# STM32_MCU.net
KiCad netlist of a schematic drawn in Altium Designer
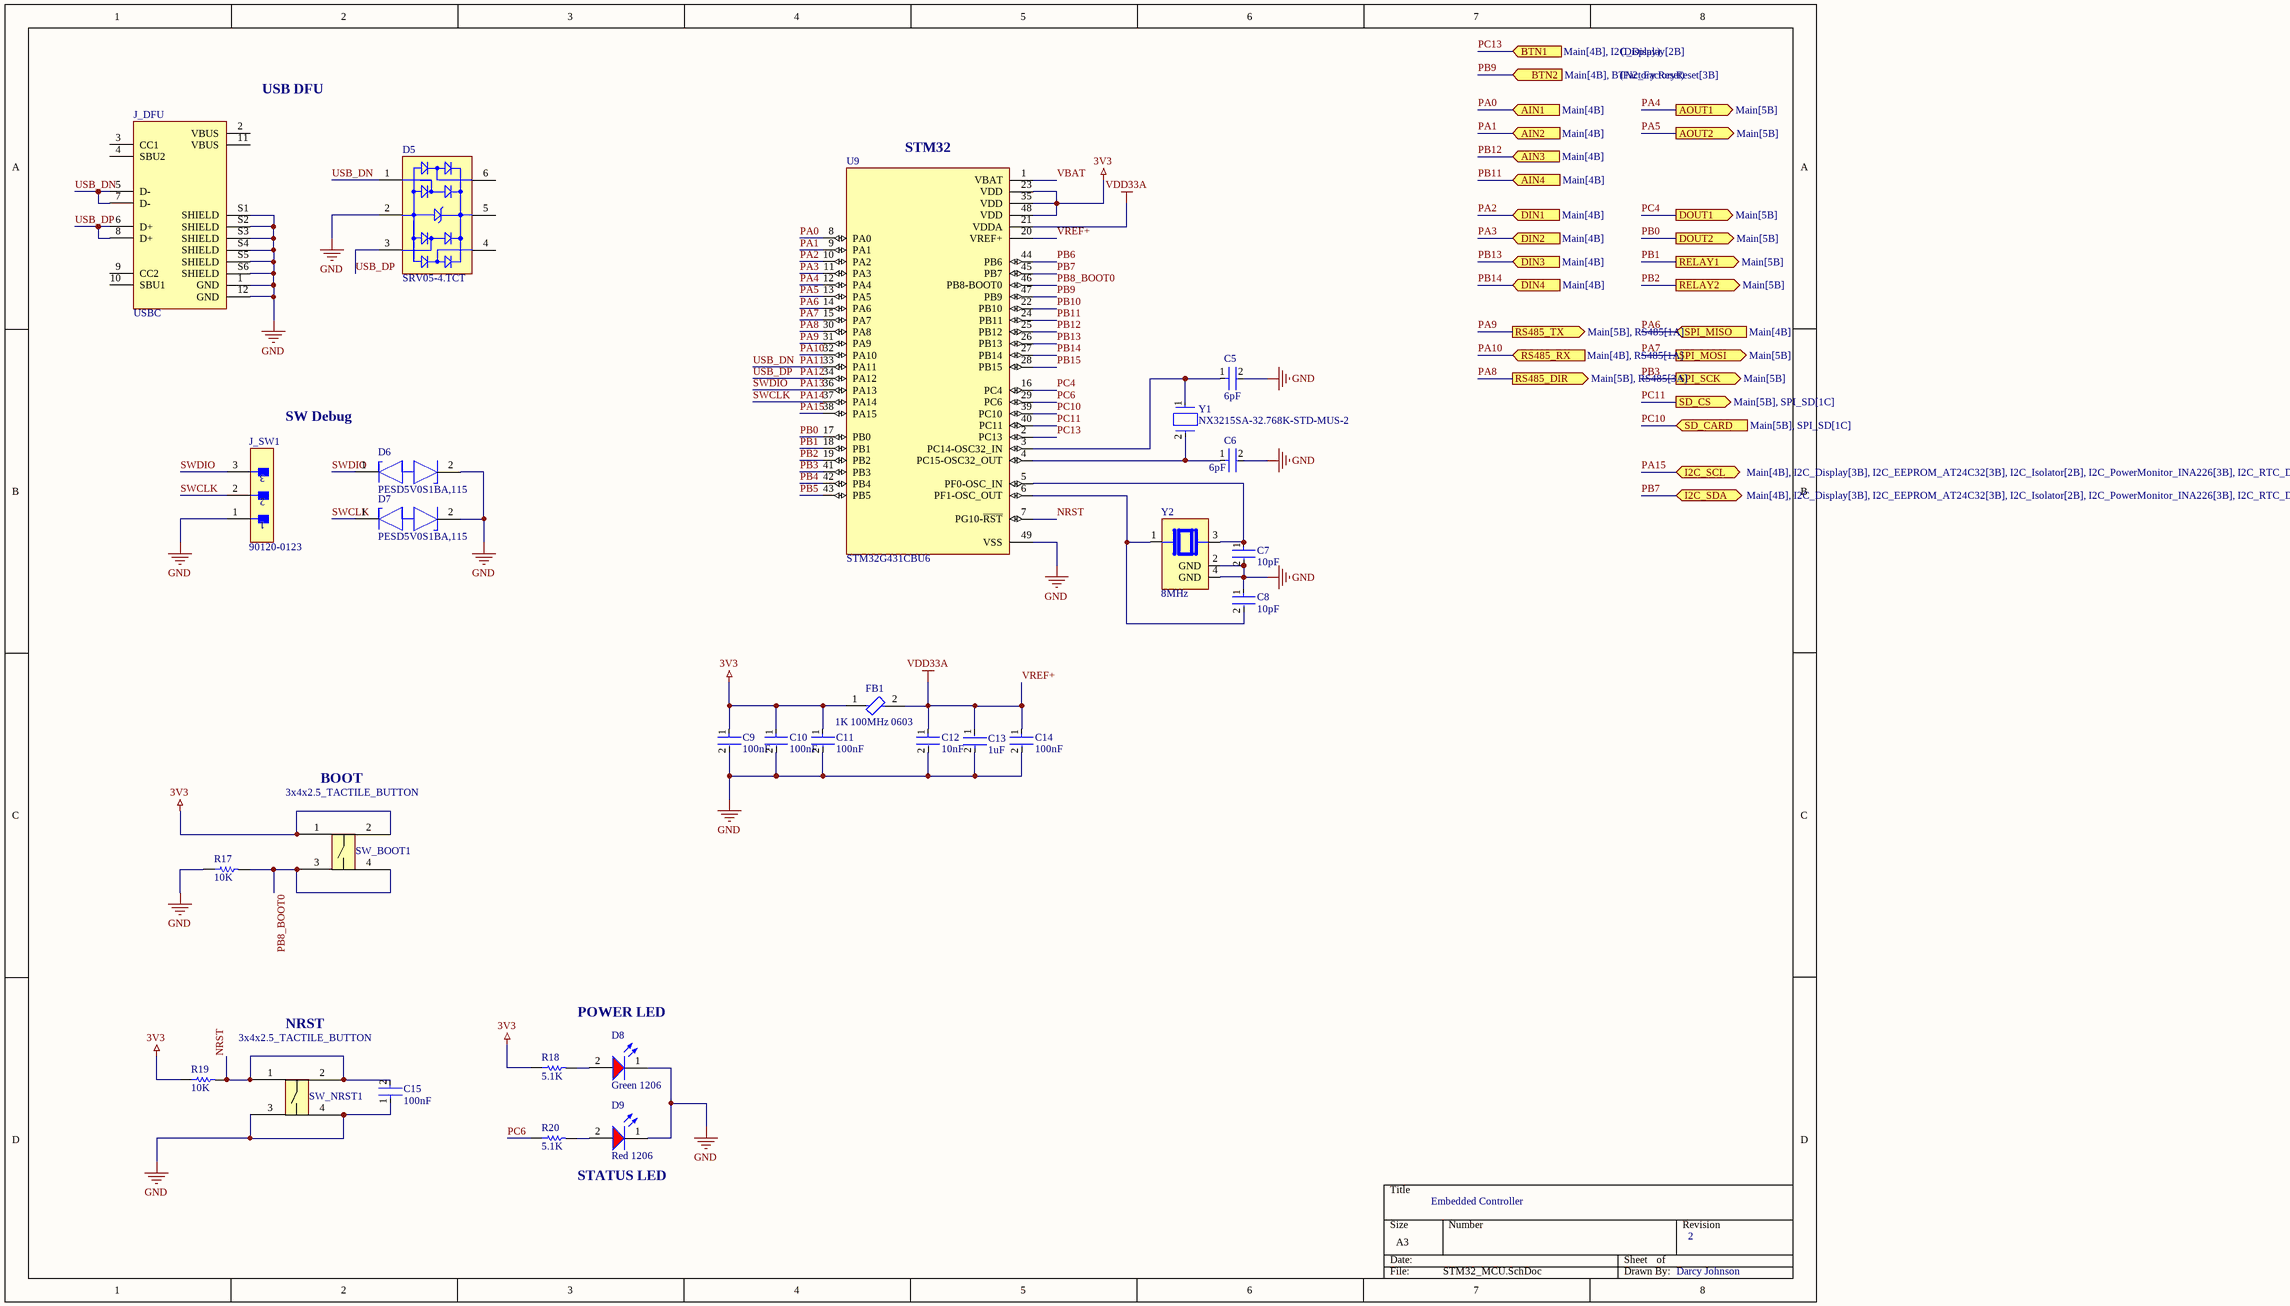
[diagram p0: STM32_MCU.SchDoc]

(export (version "E")
  (design (tool "Eeschema 10.0.6"))
  (components
    (comp (ref "C5")
      (value "6pF")
      (footprint "FP-CGA3E-0_3-0_1-MFG")
      (description "Cap Ceramic 6pF 50V C0G 0.5pF Pad SMD 0603 +125°C Automotive T/R")
      (libsource (lib "Altium Content Vault") (part "b4654b650e69147ec39a6b967a45e02"))
    )
    (comp (ref "C6")
      (value "6pF")
      (footprint "FP-CGA3E-0_3-0_1-MFG")
      (description "Cap Ceramic 6pF 50V C0G 0.5pF Pad SMD 0603 +125°C Automotive T/R")
      (libsource (lib "Altium Content Vault") (part "b4654b650e69147ec39a6b967a45e02"))
    )
    (comp (ref "C7")
      (value "10pF")
      (footprint "FP-C0603C-CF-MFG")
      (description "CAP CER 10PF 50V NP0 0603")
      (fields (field (name "MANUFACTURER") "KEMET") (field (name "TOLERANCE") "0.25 pF"))
      (libsource (lib "Altium Content Vault") (part "b4654b650e69147ec39a6b967a45e02"))
    )
    (comp (ref "C8")
      (value "10pF")
      (footprint "FP-C0603C-CF-MFG")
      (description "CAP CER 10PF 50V NP0 0603")
      (fields (field (name "MANUFACTURER") "KEMET") (field (name "TOLERANCE") "0.25 pF"))
      (libsource (lib "Altium Content Vault") (part "b4654b650e69147ec39a6b967a45e02"))
    )
    (comp (ref "C9")
      (value "100nF")
      (footprint "FP-CGA3E-0_3-0_1-IPC_A")
      (description "Cap Ceramic 100nF 50V X7R 10% Pad SMD 0603 +125°C Automotive T/R")
      (fields (field (name "TOLERANCE") "10%") (field (name "VOLTAGE") "50V"))
      (libsource (lib "Altium Content Vault") (part "b4654b650e69147ec39a6b967a45e02"))
    )
    (comp (ref "C10")
      (value "100nF")
      (footprint "FP-CGA3E-0_3-0_1-IPC_A")
      (description "Cap Ceramic 100nF 50V X7R 10% Pad SMD 0603 +125°C Automotive T/R")
      (fields (field (name "TOLERANCE") "10%") (field (name "VOLTAGE") "50V"))
      (libsource (lib "Altium Content Vault") (part "b4654b650e69147ec39a6b967a45e02"))
    )
    (comp (ref "C11")
      (value "100nF")
      (footprint "FP-CGA3E-0_3-0_1-IPC_A")
      (description "Cap Ceramic 100nF 50V X7R 10% Pad SMD 0603 +125°C Automotive T/R")
      (fields (field (name "TOLERANCE") "10%") (field (name "VOLTAGE") "50V"))
      (libsource (lib "Altium Content Vault") (part "b4654b650e69147ec39a6b967a45e02"))
    )
    (comp (ref "C12")
      (value "10nF")
      (footprint "FP-CC0603-DA-MFG")
      (description "CAP CER 10000PF 50V X7R 0603")
      (fields (field (name "TOLERANCE") "0.1") (field (name "MANUFACTURER PART NUMBER") "CC0603KRX7R9BB103"))
      (libsource (lib "Altium Content Vault") (part "11868f565c42a9108669ba33697ecf6"))
    )
    (comp (ref "C13")
      (value "1uF")
      (footprint "FP-C1608-080-0_1-IPC_B")
      (description "Multilayer Ceramic Capacitors 1μF ±10% 50V X5R SMD 0603")
      (fields (field (name "VOLTAGE") "50V") (field (name "TOLERANCE") "10%"))
      (libsource (lib "Altium Content Vault") (part "236180d848d6139a670b325ea6854c9"))
    )
    (comp (ref "C14")
      (value "100nF")
      (footprint "FP-CGA3E-0_3-0_1-IPC_A")
      (description "Cap Ceramic 100nF 50V X7R 10% Pad SMD 0603 +125°C Automotive T/R")
      (fields (field (name "TOLERANCE") "10%") (field (name "VOLTAGE") "50V"))
      (libsource (lib "Altium Content Vault") (part "b4654b650e69147ec39a6b967a45e02"))
    )
    (comp (ref "C15")
      (value "100nF")
      (footprint "FP-CGA3E-0_3-0_1-IPC_A")
      (description "Cap Ceramic 100nF 50V X7R 10% Pad SMD 0603 +125°C Automotive T/R")
      (fields (field (name "TOLERANCE") "10%") (field (name "VOLTAGE") "50V"))
      (libsource (lib "Altium Content Vault") (part "b4654b650e69147ec39a6b967a45e02"))
    )
    (comp (ref "D5")
      (value "SRV05-4.TCT")
      (footprint "SMTC-SOT23-6_V")
      (fields (field (name "MANUFACTURER") "Semtech"))
      (libsource (lib "Altium Content Vault") (part "STM-USB_DVI_HDMIULC6-4SC6X-SOT23-6L"))
    )
    (comp (ref "D6")
      (value "PESD5V0S1BA,115")
      (footprint "FP-SOD323-CA-MFG")
      (description "TVS DIODE 5V 14V SOD323")
      (libsource (lib "Altium Content Vault") (part "f6dbb2535d6b2d347ec798cb4d032a4"))
    )
    (comp (ref "D7")
      (value "PESD5V0S1BA,115")
      (footprint "FP-SOD323-CA-MFG")
      (description "TVS DIODE 5V 14V SOD323")
      (libsource (lib "Altium Content Vault") (part "f6dbb2535d6b2d347ec798cb4d032a4"))
    )
    (comp (ref "D8")
      (value "Green 1206")
      (footprint "WL-SMCW_1206_150120xx75000")
      (description "Led, Red, 630 Nm, 1.9 V, 30 Ma, 60 Mcd Rohs Compliant: Yes")
      (libsource (lib "Altium Content Vault") (part "LED_Red_2A-1K"))
    )
    (comp (ref "D9")
      (value "Red 1206")
      (footprint "WL-SMCW_1206_150120xx75000")
      (description "Led, Red, 630 Nm, 1.9 V, 30 Ma, 60 Mcd Rohs Compliant: Yes")
      (libsource (lib "Altium Content Vault") (part "LED_Red_2A-1K"))
    )
    (comp (ref "FB1")
      (value "1K 100MHz 0603")
      (footprint "FP-BLM18-0_15-t0_8-MFG")
      (description "Chip Ferrite Bead, 0603, 1000Ω @ 100MHz, 0.5Ω, 25%, 450mA")
      (fields (field (name "TOLERANCE") "25%"))
      (libsource (lib "Altium Content Vault") (part "5f30dd21d616792df468990f7003faa"))
    )
    (comp (ref "J_DFU")
      (value "USBC")
      (footprint "JAE_DX07S016JA1R1500")
      (fields (field (name "MP") "DX07S016JA1R1500"))
      (libsource (lib "USBC_Fixed") (part "DX07S016JA1R1500"))
    )
    (comp (ref "J_SW1")
      (value "90120-0123")
      (footprint "FP-90120-0123-MFG")
      (description "CONN HEADER VERT 3POS 2.54MM")
      (libsource (lib "Altium Content Vault") (part "0d3f023dd272f625e17a2be33dea85f"))
    )
    (comp (ref "R17")
      (value "10K")
      (footprint "RESC1609X55X30LL15T15")
      (description "Chip Resistor, 10 KOhm, +/- 1%, 0.1 W, -55 to 155 degC, 0603 (1608 Metric), RoHS, Tape and Reel")
      (fields (field (name "TOLERANCE") "1%") (field (name "MANUFACTURER") "Panasonic"))
      (libsource (lib "Altium Content Vault") (part "RES-2"))
    )
    (comp (ref "R18")
      (value "5.1K")
      (footprint "RESC1608X55X30LL15T15")
      (fields (field (name "PART NUMBER") "ERJ-3GEYJ512V") (field (name "MANUFACTURER") "Panasonic"))
      (libsource (lib "Altium Content Vault") (part "RES"))
    )
    (comp (ref "R19")
      (value "10K")
      (footprint "RESC1609X55X30LL15T15")
      (description "Chip Resistor, 10 KOhm, +/- 1%, 0.1 W, -55 to 155 degC, 0603 (1608 Metric), RoHS, Tape and Reel")
      (fields (field (name "TOLERANCE") "1%") (field (name "MANUFACTURER") "Panasonic"))
      (libsource (lib "Altium Content Vault") (part "RES-2"))
    )
    (comp (ref "R20")
      (value "5.1K")
      (footprint "RESC1608X55X30LL15T15")
      (fields (field (name "PART NUMBER") "ERJ-3GEYJ512V") (field (name "MANUFACTURER") "Panasonic"))
      (libsource (lib "Altium Content Vault") (part "RES"))
    )
    (comp (ref "SW_BOOT1")
      (value "3x4x2.5_TACTILE_BUTTON")
      (footprint "3x4x2.5_TACTILE_BUTTON")
      (libsource (lib "3x4x2.5_TACTILE_BUTTON") (part "3x4x2.5_TACTILE_BUTTON"))
    )
    (comp (ref "SW_NRST1")
      (value "3x4x2.5_TACTILE_BUTTON")
      (footprint "3x4x2.5_TACTILE_BUTTON")
      (libsource (lib "3x4x2.5_TACTILE_BUTTON") (part "3x4x2.5_TACTILE_BUTTON"))
    )
    (comp (ref "U9")
      (value "STM32G431CBU6")
      (footprint "QFN50P700X700X60-49N")
      (fields (field (name "MF") "STMicroelectronics"))
      (libsource (lib "STM32G431CBU6") (part "STM32G431CBU6"))
    )
    (comp (ref "Y1")
      (value "NX3215SA-32.768K-STD-MUS-2")
      (footprint "FP-NX3215SA-MFG")
      (description "CRYSTAL 32.7680KHZ 12.5PF SMD")
      (libsource (lib "Altium Content Vault") (part "c23a69dc6c9e2f18f2079038eb95dd1"))
    )
    (comp (ref "Y2")
      (value "8MHz")
      (footprint "XTAL_C3E-8.000-10-1020-M")
      (fields (field (name "MP") "C3E-8.000-10-1020-M"))
      (libsource (lib "C3E-8.000-10-1020-M") (part "C3E-8.000-10-1020-M"))
    )
  )
  (nets
    (net (code "1") (name "/NRST") (class "Default")
      (node (ref "C15") (pin "2") (pinfunction "2_2") (pintype "passive"))
      (node (ref "R19") (pin "2") (pinfunction "2_2") (pintype "passive"))
      (node (ref "SW_NRST1") (pin "1") (pinfunction "1_1") (pintype "passive"))
      (node (ref "SW_NRST1") (pin "2") (pinfunction "2_2") (pintype "passive"))
      (node (ref "U9") (pin "7") (pinfunction "PG10-~{RST}_7") (pintype "bidirectional"))
    )
    (net (code "2") (name "/PA0") (class "Default")
      (node (ref "U9") (pin "8") (pinfunction "PA0_8") (pintype "bidirectional"))
    )
    (net (code "3") (name "/PA1") (class "Default")
      (node (ref "U9") (pin "9") (pinfunction "PA1_9") (pintype "bidirectional"))
    )
    (net (code "4") (name "/PA2") (class "Default")
      (node (ref "U9") (pin "10") (pinfunction "PA2_10") (pintype "bidirectional"))
    )
    (net (code "5") (name "/PA3") (class "Default")
      (node (ref "U9") (pin "11") (pinfunction "PA3_11") (pintype "bidirectional"))
    )
    (net (code "6") (name "/PA4") (class "Default")
      (node (ref "U9") (pin "12") (pinfunction "PA4_12") (pintype "bidirectional"))
    )
    (net (code "7") (name "/PA5") (class "Default")
      (node (ref "U9") (pin "13") (pinfunction "PA5_13") (pintype "bidirectional"))
    )
    (net (code "8") (name "/PA6") (class "Default")
      (node (ref "U9") (pin "14") (pinfunction "PA6_14") (pintype "bidirectional"))
    )
    (net (code "9") (name "/PA7") (class "Default")
      (node (ref "U9") (pin "15") (pinfunction "PA7_15") (pintype "bidirectional"))
    )
    (net (code "10") (name "/PA8") (class "Default")
      (node (ref "U9") (pin "30") (pinfunction "PA8_30") (pintype "bidirectional"))
    )
    (net (code "11") (name "/PA9") (class "Default")
      (node (ref "U9") (pin "31") (pinfunction "PA9_31") (pintype "bidirectional"))
    )
    (net (code "12") (name "/PA10") (class "Default")
      (node (ref "U9") (pin "32") (pinfunction "PA10_32") (pintype "bidirectional"))
    )
    (net (code "13") (name "/PA11") (class "Default")
      (node (ref "D5") (pin "1") (pinfunction "I/O_1_1") (pintype "passive"))
      (node (ref "J_DFU") (pin "5") (pinfunction "D-_5") (pintype "passive"))
      (node (ref "J_DFU") (pin "7") (pinfunction "D-_7") (pintype "passive"))
      (node (ref "U9") (pin "33") (pinfunction "PA11_33") (pintype "bidirectional"))
    )
    (net (code "14") (name "/PA12") (class "Default")
      (node (ref "D5") (pin "3") (pinfunction "I/O_2_3") (pintype "passive"))
      (node (ref "J_DFU") (pin "6") (pinfunction "D+_6") (pintype "passive"))
      (node (ref "J_DFU") (pin "8") (pinfunction "D+_8") (pintype "passive"))
      (node (ref "U9") (pin "34") (pinfunction "PA12_34") (pintype "bidirectional"))
    )
    (net (code "15") (name "/PA13") (class "Default")
      (node (ref "D6") (pin "1") (pinfunction "K1_1") (pintype "passive"))
      (node (ref "J_SW1") (pin "3") (pinfunction "3_3") (pintype "passive"))
      (node (ref "U9") (pin "36") (pinfunction "PA13_36") (pintype "bidirectional"))
    )
    (net (code "16") (name "/PA14") (class "Default")
      (node (ref "D7") (pin "1") (pinfunction "K1_1") (pintype "passive"))
      (node (ref "J_SW1") (pin "2") (pinfunction "2_2") (pintype "passive"))
      (node (ref "U9") (pin "37") (pinfunction "PA14_37") (pintype "bidirectional"))
    )
    (net (code "17") (name "/PA15") (class "Default")
      (node (ref "U9") (pin "38") (pinfunction "PA15_38") (pintype "bidirectional"))
    )
    (net (code "18") (name "/PB0") (class "Default")
      (node (ref "U9") (pin "17") (pinfunction "PB0_17") (pintype "bidirectional"))
    )
    (net (code "19") (name "/PB1") (class "Default")
      (node (ref "U9") (pin "18") (pinfunction "PB1_18") (pintype "bidirectional"))
    )
    (net (code "20") (name "/PB2") (class "Default")
      (node (ref "U9") (pin "19") (pinfunction "PB2_19") (pintype "bidirectional"))
    )
    (net (code "21") (name "/PB3") (class "Default")
      (node (ref "U9") (pin "41") (pinfunction "PB3_41") (pintype "bidirectional"))
    )
    (net (code "22") (name "/PB4") (class "Default")
      (node (ref "U9") (pin "42") (pinfunction "PB4_42") (pintype "bidirectional"))
    )
    (net (code "23") (name "/PB5") (class "Default")
      (node (ref "U9") (pin "43") (pinfunction "PB5_43") (pintype "bidirectional"))
    )
    (net (code "24") (name "/PB6") (class "Default")
      (node (ref "U9") (pin "44") (pinfunction "PB6_44") (pintype "bidirectional"))
    )
    (net (code "25") (name "/PB7") (class "Default")
      (node (ref "U9") (pin "45") (pinfunction "PB7_45") (pintype "bidirectional"))
    )
    (net (code "26") (name "/PB8_BOOT0") (class "Default")
      (node (ref "R17") (pin "2") (pinfunction "2_2") (pintype "passive"))
      (node (ref "SW_BOOT1") (pin "3") (pinfunction "3_3") (pintype "passive"))
      (node (ref "SW_BOOT1") (pin "4") (pinfunction "4_4") (pintype "passive"))
      (node (ref "U9") (pin "46") (pinfunction "PB8-BOOT0_46") (pintype "bidirectional"))
    )
    (net (code "27") (name "/PB9") (class "Default")
      (node (ref "U9") (pin "47") (pinfunction "PB9_47") (pintype "bidirectional"))
    )
    (net (code "28") (name "/PB10") (class "Default")
      (node (ref "U9") (pin "22") (pinfunction "PB10_22") (pintype "bidirectional"))
    )
    (net (code "29") (name "/PB11") (class "Default")
      (node (ref "U9") (pin "24") (pinfunction "PB11_24") (pintype "bidirectional"))
    )
    (net (code "30") (name "/PB12") (class "Default")
      (node (ref "U9") (pin "25") (pinfunction "PB12_25") (pintype "bidirectional"))
    )
    (net (code "31") (name "/PB13") (class "Default")
      (node (ref "U9") (pin "26") (pinfunction "PB13_26") (pintype "bidirectional"))
    )
    (net (code "32") (name "/PB14") (class "Default")
      (node (ref "U9") (pin "27") (pinfunction "PB14_27") (pintype "bidirectional"))
    )
    (net (code "33") (name "/PB15") (class "Default")
      (node (ref "U9") (pin "28") (pinfunction "PB15_28") (pintype "bidirectional"))
    )
    (net (code "34") (name "/PC4") (class "Default")
      (node (ref "U9") (pin "16") (pinfunction "PC4_16") (pintype "bidirectional"))
    )
    (net (code "35") (name "/PC6") (class "Default")
      (node (ref "R20") (pin "1") (pinfunction "1_1") (pintype "passive"))
      (node (ref "U9") (pin "29") (pinfunction "PC6_29") (pintype "bidirectional"))
    )
    (net (code "36") (name "/PC10") (class "Default")
      (node (ref "U9") (pin "39") (pinfunction "PC10_39") (pintype "bidirectional"))
    )
    (net (code "37") (name "/PC11") (class "Default")
      (node (ref "U9") (pin "40") (pinfunction "PC11_40") (pintype "bidirectional"))
    )
    (net (code "38") (name "/PC13") (class "Default")
      (node (ref "U9") (pin "2") (pinfunction "PC13_2") (pintype "bidirectional"))
    )
    (net (code "39") (name "/VBAT") (class "Default")
      (node (ref "U9") (pin "1") (pinfunction "VBAT_1") (pintype "power_in"))
    )
    (net (code "40") (name "3V3") (class "Default")
      (node (ref "C10") (pin "1") (pinfunction "1_1") (pintype "passive"))
      (node (ref "C11") (pin "1") (pinfunction "1_1") (pintype "passive"))
      (node (ref "C9") (pin "1") (pinfunction "1_1") (pintype "passive"))
      (node (ref "FB1") (pin "1") (pinfunction "1_1") (pintype "passive"))
      (node (ref "R18") (pin "1") (pinfunction "1_1") (pintype "passive"))
      (node (ref "R19") (pin "1") (pinfunction "1_1") (pintype "passive"))
      (node (ref "SW_BOOT1") (pin "1") (pinfunction "1_1") (pintype "passive"))
      (node (ref "SW_BOOT1") (pin "2") (pinfunction "2_2") (pintype "passive"))
      (node (ref "U9") (pin "23") (pinfunction "VDD_23") (pintype "power_in"))
      (node (ref "U9") (pin "35") (pinfunction "VDD_35") (pintype "power_in"))
      (node (ref "U9") (pin "48") (pinfunction "VDD_48") (pintype "power_in"))
    )
    (net (code "41") (name "GND") (class "Default")
      (node (ref "C10") (pin "2") (pinfunction "2_2") (pintype "passive"))
      (node (ref "C11") (pin "2") (pinfunction "2_2") (pintype "passive"))
      (node (ref "C12") (pin "2") (pinfunction "2_2") (pintype "passive"))
      (node (ref "C13") (pin "2") (pinfunction "2_2") (pintype "passive"))
      (node (ref "C14") (pin "2") (pinfunction "2_2") (pintype "passive"))
      (node (ref "C15") (pin "1") (pinfunction "1_1") (pintype "passive"))
      (node (ref "C5") (pin "2") (pinfunction "2_2") (pintype "passive"))
      (node (ref "C6") (pin "2") (pinfunction "2_2") (pintype "passive"))
      (node (ref "C7") (pin "2") (pinfunction "2_2") (pintype "passive"))
      (node (ref "C8") (pin "1") (pinfunction "1_1") (pintype "passive"))
      (node (ref "C9") (pin "2") (pinfunction "2_2") (pintype "passive"))
      (node (ref "D5") (pin "2") (pinfunction "GND_2") (pintype "passive"))
      (node (ref "D6") (pin "2") (pinfunction "K2_2") (pintype "passive"))
      (node (ref "D7") (pin "2") (pinfunction "K2_2") (pintype "passive"))
      (node (ref "D8") (pin "1") (pinfunction "K_1") (pintype "passive"))
      (node (ref "D9") (pin "1") (pinfunction "K_1") (pintype "passive"))
      (node (ref "J_DFU") (pin "1") (pinfunction "GND_1") (pintype "power_in"))
      (node (ref "J_DFU") (pin "12") (pinfunction "GND_12") (pintype "power_in"))
      (node (ref "J_DFU") (pin "S1") (pinfunction "SHIELD_S1") (pintype "passive"))
      (node (ref "J_DFU") (pin "S2") (pinfunction "SHIELD_S2") (pintype "passive"))
      (node (ref "J_DFU") (pin "S3") (pinfunction "SHIELD_S3") (pintype "passive"))
      (node (ref "J_DFU") (pin "S4") (pinfunction "SHIELD_S4") (pintype "passive"))
      (node (ref "J_DFU") (pin "S5") (pinfunction "SHIELD_S5") (pintype "passive"))
      (node (ref "J_DFU") (pin "S6") (pinfunction "SHIELD_S6") (pintype "passive"))
      (node (ref "J_SW1") (pin "1") (pinfunction "1_1") (pintype "passive"))
      (node (ref "R17") (pin "1") (pinfunction "1_1") (pintype "passive"))
      (node (ref "SW_NRST1") (pin "3") (pinfunction "3_3") (pintype "passive"))
      (node (ref "SW_NRST1") (pin "4") (pinfunction "4_4") (pintype "passive"))
      (node (ref "U9") (pin "49") (pinfunction "VSS_49") (pintype "power_in"))
      (node (ref "Y2") (pin "2") (pinfunction "GND_2") (pintype "power_in"))
      (node (ref "Y2") (pin "4") (pinfunction "GND_4") (pintype "power_in"))
    )
    (net (code "42") (name "Net-(D8-A)") (class "Default")
      (node (ref "D8") (pin "2") (pinfunction "A_2") (pintype "passive"))
      (node (ref "R18") (pin "2") (pinfunction "2_2") (pintype "passive"))
    )
    (net (code "43") (name "Net-(D9-A)") (class "Default")
      (node (ref "D9") (pin "2") (pinfunction "A_2") (pintype "passive"))
      (node (ref "R20") (pin "2") (pinfunction "2_2") (pintype "passive"))
    )
    (net (code "44") (name "Net-(U9-PC14-OSC32_IN)") (class "Default")
      (node (ref "C5") (pin "1") (pinfunction "1_1") (pintype "passive"))
      (node (ref "U9") (pin "3") (pinfunction "PC14-OSC32_IN_3") (pintype "bidirectional"))
      (node (ref "Y1") (pin "1") (pinfunction "1_1") (pintype "passive"))
    )
    (net (code "45") (name "Net-(U9-PC15-OSC32_OUT)") (class "Default")
      (node (ref "C6") (pin "1") (pinfunction "1_1") (pintype "passive"))
      (node (ref "U9") (pin "4") (pinfunction "PC15-OSC32_OUT_4") (pintype "bidirectional"))
      (node (ref "Y1") (pin "2") (pinfunction "2_2") (pintype "passive"))
    )
    (net (code "46") (name "Net-(U9-PF0-OSC_IN)") (class "Default")
      (node (ref "C7") (pin "1") (pinfunction "1_1") (pintype "passive"))
      (node (ref "U9") (pin "5") (pinfunction "PF0-OSC_IN_5") (pintype "bidirectional"))
      (node (ref "Y2") (pin "3") (pinfunction "3_3") (pintype "passive"))
    )
    (net (code "47") (name "Net-(U9-PF1-OSC_OUT)") (class "Default")
      (node (ref "C8") (pin "2") (pinfunction "2_2") (pintype "passive"))
      (node (ref "U9") (pin "6") (pinfunction "PF1-OSC_OUT_6") (pintype "bidirectional"))
      (node (ref "Y2") (pin "1") (pinfunction "1_1") (pintype "passive"))
    )
    (net (code "48") (name "VDD33A") (class "Default")
      (node (ref "C12") (pin "1") (pinfunction "1_1") (pintype "passive"))
      (node (ref "C13") (pin "1") (pinfunction "1_1") (pintype "passive"))
      (node (ref "C14") (pin "1") (pinfunction "1_1") (pintype "passive"))
      (node (ref "FB1") (pin "2") (pinfunction "2_2") (pintype "passive"))
      (node (ref "U9") (pin "20") (pinfunction "VREF+_20") (pintype "power_in"))
      (node (ref "U9") (pin "21") (pinfunction "VDDA_21") (pintype "power_in"))
    )
    (net (code "49") (name "unconnected-(D5-I{slash}O_3-Pad4)") (class "Default")
      (node (ref "D5") (pin "4") (pinfunction "I/O_3_4") (pintype "passive"))
    )
    (net (code "50") (name "unconnected-(D5-I{slash}O_4-Pad6)") (class "Default")
      (node (ref "D5") (pin "6") (pinfunction "I/O_4_6") (pintype "passive"))
    )
    (net (code "51") (name "unconnected-(D5-VBUS-Pad5)") (class "Default")
      (node (ref "D5") (pin "5") (pinfunction "VBUS_5") (pintype "passive"))
    )
    (net (code "52") (name "unconnected-(J_DFU-CC1-Pad3)") (class "Default")
      (node (ref "J_DFU") (pin "3") (pinfunction "CC1_3") (pintype "passive"))
    )
    (net (code "53") (name "unconnected-(J_DFU-CC2-Pad9)") (class "Default")
      (node (ref "J_DFU") (pin "9") (pinfunction "CC2_9") (pintype "passive"))
    )
    (net (code "54") (name "unconnected-(J_DFU-SBU1-Pad10)") (class "Default")
      (node (ref "J_DFU") (pin "10") (pinfunction "SBU1_10") (pintype "passive"))
    )
    (net (code "55") (name "unconnected-(J_DFU-SBU2-Pad4)") (class "Default")
      (node (ref "J_DFU") (pin "4") (pinfunction "SBU2_4") (pintype "passive"))
    )
    (net (code "56") (name "unconnected-(J_DFU-VBUS-Pad2)") (class "Default")
      (node (ref "J_DFU") (pin "2") (pinfunction "VBUS_2") (pintype "power_in"))
    )
    (net (code "57") (name "unconnected-(J_DFU-VBUS-Pad11)") (class "Default")
      (node (ref "J_DFU") (pin "11") (pinfunction "VBUS_11") (pintype "power_in"))
    )
  )
)
